# working.net
KiCad netlist of a schematic drawn in EAGLE
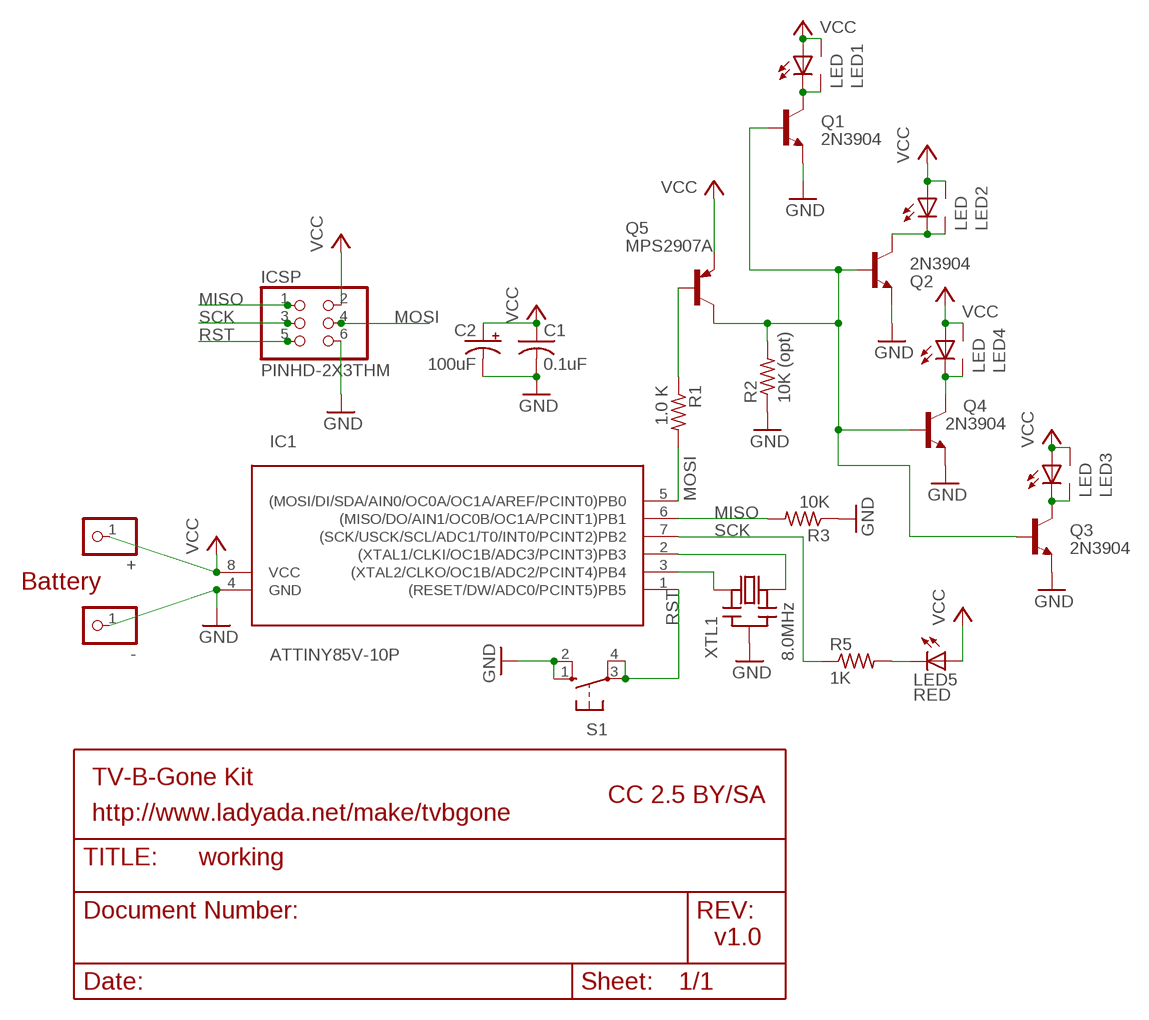
[diagram p0: schematic, sheet 1]

(export (version "E")
  (design (tool "Eeschema 10.0.6"))
  (components
    (comp (ref "+")
      (value "PINHD-1X1")
      (footprint "eagle-import:1X01")
      (libsource (lib "eagle-import") (part "PINHD-1X1"))
    )
    (comp (ref "-")
      (value "PINHD-1X1")
      (footprint "eagle-import:1X01")
      (libsource (lib "eagle-import") (part "PINHD-1X1"))
    )
    (comp (ref "C1")
      (value "0.1uF")
      (footprint "eagle-import:C025-025X050")
      (libsource (lib "eagle-import") (part "C-US025-025X050"))
    )
    (comp (ref "C2")
      (value "100uF")
      (footprint "eagle-import:E2,5-5")
      (libsource (lib "eagle-import") (part "CPOL-USE2.5-5"))
    )
    (comp (ref "IC1")
      (value "ATTINY85V-10P")
      (footprint "eagle-import:DIL08")
      (libsource (lib "eagle-import") (part "ATTINY85PV-10"))
    )
    (comp (ref "ICSP")
      (value "PINHD-2X3THM")
      (footprint "eagle-import:ISP6")
      (libsource (lib "eagle-import") (part "PINHD-2X3THM"))
    )
    (comp (ref "LED1")
      (value "LED")
      (footprint "eagle-import:5MM-SIDE")
      (libsource (lib "eagle-import") (part "tvbgone_LED"))
    )
    (comp (ref "LED2")
      (value "LED")
      (footprint "eagle-import:5MM-SIDE")
      (libsource (lib "eagle-import") (part "tvbgone_LED"))
    )
    (comp (ref "LED3")
      (value "LED")
      (footprint "eagle-import:5MM-SIDE")
      (libsource (lib "eagle-import") (part "tvbgone_LED"))
    )
    (comp (ref "LED4")
      (value "LED")
      (footprint "eagle-import:5MM-SIDE")
      (libsource (lib "eagle-import") (part "tvbgone_LED"))
    )
    (comp (ref "LED5")
      (value "RED")
      (footprint "eagle-import:LED3MM")
      (libsource (lib "eagle-import") (part "LED3MM"))
    )
    (comp (ref "Q1")
      (value "2N3904")
      (footprint "eagle-import:TO92-EZ")
      (libsource (lib "eagle-import") (part "2N3904EZ"))
    )
    (comp (ref "Q2")
      (value "2N3904")
      (footprint "eagle-import:TO92-EZ")
      (libsource (lib "eagle-import") (part "2N3904EZ"))
    )
    (comp (ref "Q3")
      (value "2N3904")
      (footprint "eagle-import:TO92-EZ")
      (libsource (lib "eagle-import") (part "2N3904EZ"))
    )
    (comp (ref "Q4")
      (value "2N3904")
      (footprint "eagle-import:TO92-EZ")
      (libsource (lib "eagle-import") (part "2N3904EZ"))
    )
    (comp (ref "Q5")
      (value "MPS2907A")
      (footprint "eagle-import:TO92-CBE")
      (libsource (lib "eagle-import") (part "MPS2907A"))
    )
    (comp (ref "R1")
      (value "1.0 K")
      (footprint "eagle-import:0207_10")
      (libsource (lib "eagle-import") (part "R-US_0207/10"))
    )
    (comp (ref "R2")
      (value "10K (opt)")
      (footprint "eagle-import:0207_10")
      (libsource (lib "eagle-import") (part "R-US_0207/10"))
    )
    (comp (ref "R3")
      (value "10K")
      (footprint "eagle-import:0207_10")
      (libsource (lib "eagle-import") (part "R-US_0207/10"))
    )
    (comp (ref "R5")
      (value "1K")
      (footprint "eagle-import:0207_10")
      (libsource (lib "eagle-import") (part "R-US_0207/10"))
    )
    (comp (ref "S1")
      (value "10-XX")
      (footprint "eagle-import:B3F-10XX")
      (libsource (lib "eagle-import") (part "10-XX"))
    )
    (comp (ref "XTL1")
      (value "8.0MHz")
      (footprint "eagle-import:CERM_OSC")
      (libsource (lib "eagle-import") (part "CERMOSCILL"))
    )
  )
  (nets
    (net (code "1") (name "/MISO") (class "Default")
      (node (ref "IC1") (pin "6") (pinfunction "(MISO/DO/AIN1/OC0B/OC1A/PCINT1)PB1_6") (pintype "bidirectional"))
      (node (ref "ICSP") (pin "1") (pinfunction "1_1") (pintype "passive"))
      (node (ref "R3") (pin "2") (pinfunction "2_2") (pintype "passive"))
    )
    (net (code "2") (name "/MOSI") (class "Default")
      (node (ref "IC1") (pin "5") (pinfunction "(MOSI/DI/SDA/AIN0/OC0A/OC1A/AREF/PCINT0)PB0_5") (pintype "bidirectional"))
      (node (ref "ICSP") (pin "4") (pinfunction "4_4") (pintype "passive"))
      (node (ref "R1") (pin "2") (pinfunction "2_2") (pintype "passive"))
    )
    (net (code "3") (name "/RST") (class "Default")
      (node (ref "IC1") (pin "1") (pinfunction "(RESET/DW/ADC0/PCINT5)PB5_1") (pintype "bidirectional"))
      (node (ref "ICSP") (pin "5") (pinfunction "5_5") (pintype "passive"))
      (node (ref "S1") (pin "3") (pinfunction "P_3") (pintype "passive"))
      (node (ref "S1") (pin "4") (pinfunction "P1_4") (pintype "passive"))
    )
    (net (code "4") (name "/SCK") (class "Default")
      (node (ref "IC1") (pin "7") (pinfunction "(SCK/USCK/SCL/ADC1/T0/INT0/PCINT2)PB2_7") (pintype "bidirectional"))
      (node (ref "ICSP") (pin "3") (pinfunction "3_3") (pintype "passive"))
      (node (ref "R5") (pin "1") (pinfunction "1_1") (pintype "passive"))
    )
    (net (code "5") (name "GND") (class "Default")
      (node (ref "-") (pin "1") (pinfunction "1_1") (pintype "passive"))
      (node (ref "C1") (pin "2") (pinfunction "2_2") (pintype "passive"))
      (node (ref "C2") (pin "-") (pinfunction "-_-") (pintype "passive"))
      (node (ref "IC1") (pin "4") (pinfunction "GND_4") (pintype "bidirectional"))
      (node (ref "ICSP") (pin "6") (pinfunction "6_6") (pintype "passive"))
      (node (ref "Q1") (pin "3") (pinfunction "E_3") (pintype "passive"))
      (node (ref "Q2") (pin "3") (pinfunction "E_3") (pintype "passive"))
      (node (ref "Q3") (pin "3") (pinfunction "E_3") (pintype "passive"))
      (node (ref "Q4") (pin "3") (pinfunction "E_3") (pintype "passive"))
      (node (ref "R2") (pin "1") (pinfunction "1_1") (pintype "passive"))
      (node (ref "R3") (pin "1") (pinfunction "1_1") (pintype "passive"))
      (node (ref "S1") (pin "1") (pinfunction "S_1") (pintype "passive"))
      (node (ref "S1") (pin "2") (pinfunction "S1_2") (pintype "passive"))
      (node (ref "XTL1") (pin "P$2") (pinfunction "GND_P$2") (pintype "bidirectional"))
    )
    (net (code "6") (name "Net-(IC1-(XTAL1{slash}CLKI{slash}OC1B{slash}ADC3{slash}PCINT3)PB3)") (class "Default")
      (node (ref "IC1") (pin "2") (pinfunction "(XTAL1/CLKI/OC1B/ADC3/PCINT3)PB3_2") (pintype "bidirectional"))
      (node (ref "XTL1") (pin "P$3") (pinfunction "OUT_P$3") (pintype "bidirectional"))
    )
    (net (code "7") (name "Net-(IC1-(XTAL2{slash}CLKO{slash}OC1B{slash}ADC2{slash}PCINT4)PB4)") (class "Default")
      (node (ref "IC1") (pin "3") (pinfunction "(XTAL2/CLKO/OC1B/ADC2/PCINT4)PB4_3") (pintype "bidirectional"))
      (node (ref "XTL1") (pin "P$1") (pinfunction "IN_P$1") (pintype "bidirectional"))
    )
    (net (code "8") (name "Net-(LED1-C)") (class "Default")
      (node (ref "LED1") (pin "K") (pinfunction "C_K") (pintype "passive"))
      (node (ref "LED1") (pin "K2") (pinfunction "C1_K2") (pintype "passive"))
      (node (ref "Q1") (pin "1") (pinfunction "C_1") (pintype "passive"))
    )
    (net (code "9") (name "Net-(LED2-C)") (class "Default")
      (node (ref "LED2") (pin "K") (pinfunction "C_K") (pintype "passive"))
      (node (ref "LED2") (pin "K2") (pinfunction "C1_K2") (pintype "passive"))
      (node (ref "Q2") (pin "1") (pinfunction "C_1") (pintype "passive"))
    )
    (net (code "10") (name "Net-(LED3-C)") (class "Default")
      (node (ref "LED3") (pin "K") (pinfunction "C_K") (pintype "passive"))
      (node (ref "LED3") (pin "K2") (pinfunction "C1_K2") (pintype "passive"))
      (node (ref "Q3") (pin "1") (pinfunction "C_1") (pintype "passive"))
    )
    (net (code "11") (name "Net-(LED4-C)") (class "Default")
      (node (ref "LED4") (pin "K") (pinfunction "C_K") (pintype "passive"))
      (node (ref "LED4") (pin "K2") (pinfunction "C1_K2") (pintype "passive"))
      (node (ref "Q4") (pin "1") (pinfunction "C_1") (pintype "passive"))
    )
    (net (code "12") (name "Net-(LED5-C)") (class "Default")
      (node (ref "LED5") (pin "K") (pinfunction "C_K") (pintype "passive"))
      (node (ref "R5") (pin "2") (pinfunction "2_2") (pintype "passive"))
    )
    (net (code "13") (name "Net-(Q1-B)") (class "Default")
      (node (ref "Q1") (pin "2") (pinfunction "B_2") (pintype "passive"))
      (node (ref "Q2") (pin "2") (pinfunction "B_2") (pintype "passive"))
      (node (ref "Q3") (pin "2") (pinfunction "B_2") (pintype "passive"))
      (node (ref "Q4") (pin "2") (pinfunction "B_2") (pintype "passive"))
      (node (ref "Q5") (pin "C") (pinfunction "C_C") (pintype "passive"))
      (node (ref "R2") (pin "2") (pinfunction "2_2") (pintype "passive"))
    )
    (net (code "14") (name "Net-(Q5-PadB)") (class "Default")
      (node (ref "Q5") (pin "B") (pinfunction "B_B") (pintype "passive"))
      (node (ref "R1") (pin "1") (pinfunction "1_1") (pintype "passive"))
    )
    (net (code "15") (name "VCC") (class "Default")
      (node (ref "+") (pin "1") (pinfunction "1_1") (pintype "passive"))
      (node (ref "C1") (pin "1") (pinfunction "1_1") (pintype "passive"))
      (node (ref "C2") (pin "+") (pinfunction "+_+") (pintype "passive"))
      (node (ref "IC1") (pin "8") (pinfunction "VCC_8") (pintype "bidirectional"))
      (node (ref "ICSP") (pin "2") (pinfunction "2_2") (pintype "passive"))
      (node (ref "LED1") (pin "A") (pinfunction "A_A") (pintype "passive"))
      (node (ref "LED1") (pin "A2") (pinfunction "A1_A2") (pintype "passive"))
      (node (ref "LED2") (pin "A") (pinfunction "A_A") (pintype "passive"))
      (node (ref "LED2") (pin "A2") (pinfunction "A1_A2") (pintype "passive"))
      (node (ref "LED3") (pin "A") (pinfunction "A_A") (pintype "passive"))
      (node (ref "LED3") (pin "A2") (pinfunction "A1_A2") (pintype "passive"))
      (node (ref "LED4") (pin "A") (pinfunction "A_A") (pintype "passive"))
      (node (ref "LED4") (pin "A2") (pinfunction "A1_A2") (pintype "passive"))
      (node (ref "LED5") (pin "A") (pinfunction "A_A") (pintype "passive"))
      (node (ref "Q5") (pin "E") (pinfunction "E_E") (pintype "passive"))
    )
  )
)
